# BLDC_DRIVER_DOOR.net
KiCad netlist of a schematic drawn in Altium Designer
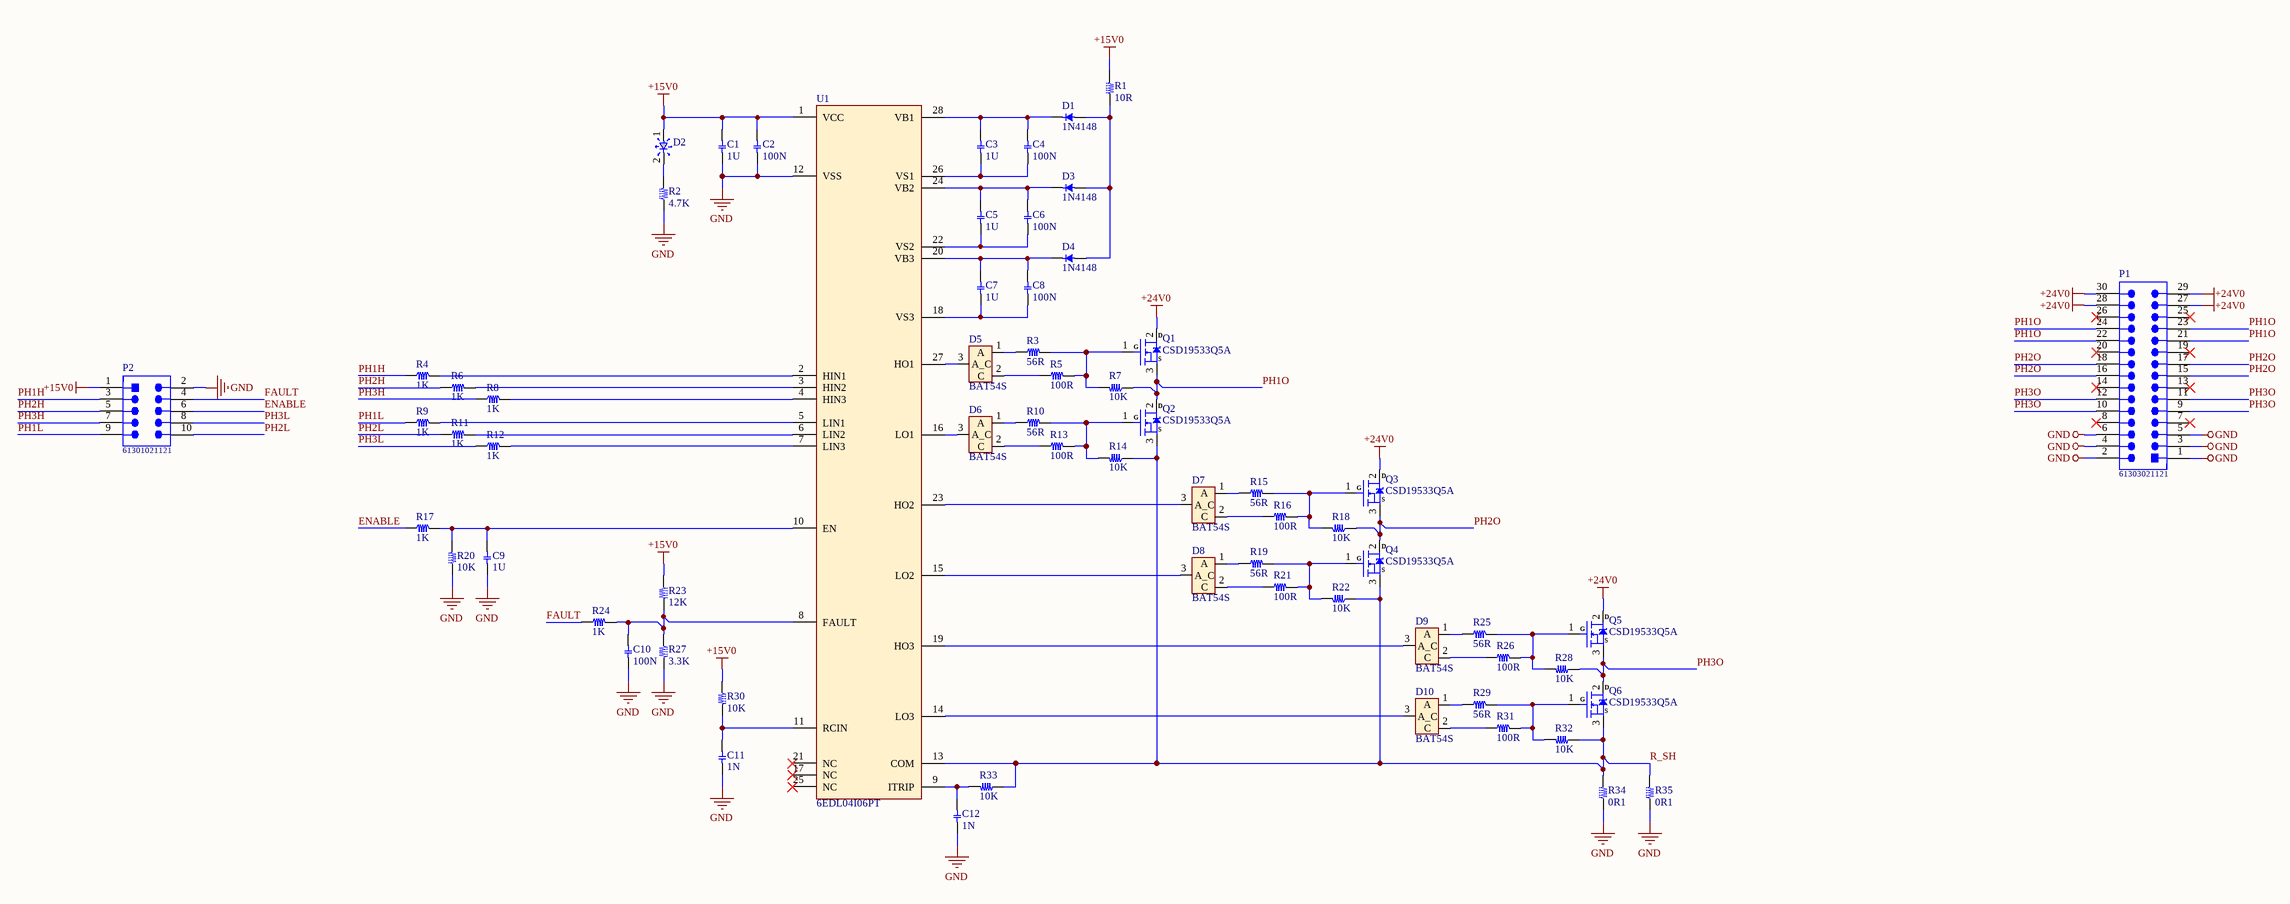
[diagram p0: BLDC_DRIVER_DOOR.SchDoc]

(export (version "E")
  (design (tool "Eeschema 10.0.6"))
  (components
    (comp (ref "C1")
      (value "1U")
      (footprint "C 0603")
      (description "CAP_SMD")
      (libsource (lib "radmehr_library") (part "CAP_SMD"))
    )
    (comp (ref "C2")
      (value "100N")
      (footprint "C 0603")
      (description "CAP_SMD")
      (libsource (lib "radmehr_library") (part "CAP_SMD"))
    )
    (comp (ref "C3")
      (value "1U")
      (footprint "C 0805")
      (description "CAP_SMD")
      (libsource (lib "radmehr_library") (part "CAP_SMD"))
    )
    (comp (ref "C4")
      (value "100N")
      (footprint "C 0805")
      (description "CAP_SMD")
      (libsource (lib "radmehr_library") (part "CAP_SMD"))
    )
    (comp (ref "C5")
      (value "1U")
      (footprint "C 0805")
      (description "CAP_SMD")
      (libsource (lib "radmehr_library") (part "CAP_SMD"))
    )
    (comp (ref "C6")
      (value "100N")
      (footprint "C 0805")
      (description "CAP_SMD")
      (libsource (lib "radmehr_library") (part "CAP_SMD"))
    )
    (comp (ref "C7")
      (value "1U")
      (footprint "C 0805")
      (description "CAP_SMD")
      (libsource (lib "radmehr_library") (part "CAP_SMD"))
    )
    (comp (ref "C8")
      (value "100N")
      (footprint "C 0805")
      (description "CAP_SMD")
      (libsource (lib "radmehr_library") (part "CAP_SMD"))
    )
    (comp (ref "C9")
      (value "1U")
      (footprint "C 0603")
      (description "CAP_SMD")
      (libsource (lib "radmehr_library") (part "CAP_SMD"))
    )
    (comp (ref "C10")
      (value "100N")
      (footprint "C 0603")
      (description "CAP_SMD")
      (libsource (lib "radmehr_library") (part "CAP_SMD"))
    )
    (comp (ref "C11")
      (value "1N")
      (footprint "C 0603")
      (description "CAP_SMD")
      (libsource (lib "radmehr_library") (part "CAP_SMD"))
    )
    (comp (ref "C12")
      (value "1N")
      (footprint "C 0805")
      (description "CAP_SMD")
      (libsource (lib "radmehr_library") (part "CAP_SMD"))
    )
    (comp (ref "D1")
      (value "1N4148")
      (footprint "D SOD-123")
      (description "DIOD_SMD")
      (libsource (lib "radmehr_library") (part "DIOD_SMD"))
    )
    (comp (ref "D2")
      (value "LED_SMD")
      (footprint "D 0603")
      (libsource (lib "radmehr_library") (part "LED_SMD"))
    )
    (comp (ref "D3")
      (value "1N4148")
      (footprint "D SOD-123")
      (description "DIOD_SMD")
      (libsource (lib "radmehr_library") (part "DIOD_SMD"))
    )
    (comp (ref "D4")
      (value "1N4148")
      (footprint "D SOD-123")
      (description "DIOD_SMD")
      (libsource (lib "radmehr_library") (part "DIOD_SMD"))
    )
    (comp (ref "D5")
      (value "BAT54S")
      (footprint "SOT-23_3_D")
      (libsource (lib "radmehr_library") (part "BAT54S"))
    )
    (comp (ref "D6")
      (value "BAT54S")
      (footprint "SOT-23_3_D")
      (libsource (lib "radmehr_library") (part "BAT54S"))
    )
    (comp (ref "D7")
      (value "BAT54S")
      (footprint "SOT-23_3_D")
      (libsource (lib "radmehr_library") (part "BAT54S"))
    )
    (comp (ref "D8")
      (value "BAT54S")
      (footprint "SOT-23_3_D")
      (libsource (lib "radmehr_library") (part "BAT54S"))
    )
    (comp (ref "D9")
      (value "BAT54S")
      (footprint "SOT-23_3_D")
      (libsource (lib "radmehr_library") (part "BAT54S"))
    )
    (comp (ref "D10")
      (value "BAT54S")
      (footprint "SOT-23_3_D")
      (libsource (lib "radmehr_library") (part "BAT54S"))
    )
    (comp (ref "P1")
      (value "61303021121")
      (footprint "61303021121")
      (description "WR-PHD Pin Header, THT, pitch 2.54mm, Dual Row, Vertical, 30p")
      (fields (field (name "MANUFACTURER") "Wurth Elektronik"))
      (libsource (lib "Altium_WR-PHD (rev22a)") (part "61303021121"))
    )
    (comp (ref "P2")
      (value "61301021121")
      (footprint "61301021121")
      (description "WR-PHD Pin Header, THT, pitch 2.54mm, Dual Row, Vertical, 10p")
      (fields (field (name "MANUFACTURER") "Wurth Elektronik"))
      (libsource (lib "Altium_WR-PHD (rev22a)") (part "61301021121"))
    )
    (comp (ref "Q1")
      (value "CSD19533Q5A")
      (footprint "Q5A")
      (libsource (lib "radmehr_library") (part "CSD19533Q5A"))
    )
    (comp (ref "Q2")
      (value "CSD19533Q5A")
      (footprint "Q5A")
      (libsource (lib "radmehr_library") (part "CSD19533Q5A"))
    )
    (comp (ref "Q3")
      (value "CSD19533Q5A")
      (footprint "Q5A")
      (libsource (lib "radmehr_library") (part "CSD19533Q5A"))
    )
    (comp (ref "Q4")
      (value "CSD19533Q5A")
      (footprint "Q5A")
      (libsource (lib "radmehr_library") (part "CSD19533Q5A"))
    )
    (comp (ref "Q5")
      (value "CSD19533Q5A")
      (footprint "Q5A")
      (libsource (lib "radmehr_library") (part "CSD19533Q5A"))
    )
    (comp (ref "Q6")
      (value "CSD19533Q5A")
      (footprint "Q5A")
      (libsource (lib "radmehr_library") (part "CSD19533Q5A"))
    )
    (comp (ref "R1")
      (value "10R")
      (footprint "R 1206")
      (description "RES_SMD")
      (libsource (lib "radmehr_library") (part "RES_SMD"))
    )
    (comp (ref "R2")
      (value "4.7K")
      (footprint "R 0603")
      (description "RES_SMD")
      (libsource (lib "radmehr_library") (part "RES_SMD"))
    )
    (comp (ref "R3")
      (value "56R")
      (footprint "R 0805")
      (description "RES_SMD")
      (libsource (lib "radmehr_library") (part "RES_SMD"))
    )
    (comp (ref "R4")
      (value "1K")
      (footprint "R 0603")
      (description "RES_SMD")
      (libsource (lib "radmehr_library") (part "RES_SMD"))
    )
    (comp (ref "R5")
      (value "100R")
      (footprint "R 0805")
      (description "RES_SMD")
      (libsource (lib "radmehr_library") (part "RES_SMD"))
    )
    (comp (ref "R6")
      (value "1K")
      (footprint "R 0603")
      (description "RES_SMD")
      (libsource (lib "radmehr_library") (part "RES_SMD"))
    )
    (comp (ref "R7")
      (value "10K")
      (footprint "R 0603")
      (description "RES_SMD")
      (libsource (lib "radmehr_library") (part "RES_SMD"))
    )
    (comp (ref "R8")
      (value "1K")
      (footprint "R 0603")
      (description "RES_SMD")
      (libsource (lib "radmehr_library") (part "RES_SMD"))
    )
    (comp (ref "R9")
      (value "1K")
      (footprint "R 0603")
      (description "RES_SMD")
      (libsource (lib "radmehr_library") (part "RES_SMD"))
    )
    (comp (ref "R10")
      (value "56R")
      (footprint "R 0805")
      (description "RES_SMD")
      (libsource (lib "radmehr_library") (part "RES_SMD"))
    )
    (comp (ref "R11")
      (value "1K")
      (footprint "R 0603")
      (description "RES_SMD")
      (libsource (lib "radmehr_library") (part "RES_SMD"))
    )
    (comp (ref "R12")
      (value "1K")
      (footprint "R 0603")
      (description "RES_SMD")
      (libsource (lib "radmehr_library") (part "RES_SMD"))
    )
    (comp (ref "R13")
      (value "100R")
      (footprint "R 0805")
      (description "RES_SMD")
      (libsource (lib "radmehr_library") (part "RES_SMD"))
    )
    (comp (ref "R14")
      (value "10K")
      (footprint "R 0603")
      (description "RES_SMD")
      (libsource (lib "radmehr_library") (part "RES_SMD"))
    )
    (comp (ref "R15")
      (value "56R")
      (footprint "R 0805")
      (description "RES_SMD")
      (libsource (lib "radmehr_library") (part "RES_SMD"))
    )
    (comp (ref "R16")
      (value "100R")
      (footprint "R 0805")
      (description "RES_SMD")
      (libsource (lib "radmehr_library") (part "RES_SMD"))
    )
    (comp (ref "R17")
      (value "1K")
      (footprint "R 0603")
      (description "RES_SMD")
      (libsource (lib "radmehr_library") (part "RES_SMD"))
    )
    (comp (ref "R18")
      (value "10K")
      (footprint "R 0603")
      (description "RES_SMD")
      (libsource (lib "radmehr_library") (part "RES_SMD"))
    )
    (comp (ref "R19")
      (value "56R")
      (footprint "R 0805")
      (description "RES_SMD")
      (libsource (lib "radmehr_library") (part "RES_SMD"))
    )
    (comp (ref "R20")
      (value "10K")
      (footprint "R 0603")
      (description "RES_SMD")
      (libsource (lib "radmehr_library") (part "RES_SMD"))
    )
    (comp (ref "R21")
      (value "100R")
      (footprint "R 0805")
      (description "RES_SMD")
      (libsource (lib "radmehr_library") (part "RES_SMD"))
    )
    (comp (ref "R22")
      (value "10K")
      (footprint "R 0603")
      (description "RES_SMD")
      (libsource (lib "radmehr_library") (part "RES_SMD"))
    )
    (comp (ref "R23")
      (value "12K")
      (footprint "R 0603")
      (description "RES_SMD")
      (libsource (lib "radmehr_library") (part "RES_SMD"))
    )
    (comp (ref "R24")
      (value "1K")
      (footprint "R 0603")
      (description "RES_SMD")
      (libsource (lib "radmehr_library") (part "RES_SMD"))
    )
    (comp (ref "R25")
      (value "56R")
      (footprint "R 0805")
      (description "RES_SMD")
      (libsource (lib "radmehr_library") (part "RES_SMD"))
    )
    (comp (ref "R26")
      (value "100R")
      (footprint "R 0805")
      (description "RES_SMD")
      (libsource (lib "radmehr_library") (part "RES_SMD"))
    )
    (comp (ref "R27")
      (value "3.3K")
      (footprint "R 0603")
      (description "RES_SMD")
      (libsource (lib "radmehr_library") (part "RES_SMD"))
    )
    (comp (ref "R28")
      (value "10K")
      (footprint "R 0603")
      (description "RES_SMD")
      (libsource (lib "radmehr_library") (part "RES_SMD"))
    )
    (comp (ref "R29")
      (value "56R")
      (footprint "R 0805")
      (description "RES_SMD")
      (libsource (lib "radmehr_library") (part "RES_SMD"))
    )
    (comp (ref "R30")
      (value "10K")
      (footprint "R 0603")
      (description "RES_SMD")
      (libsource (lib "radmehr_library") (part "RES_SMD"))
    )
    (comp (ref "R31")
      (value "100R")
      (footprint "R 0805")
      (description "RES_SMD")
      (libsource (lib "radmehr_library") (part "RES_SMD"))
    )
    (comp (ref "R32")
      (value "10K")
      (footprint "R 0603")
      (description "RES_SMD")
      (libsource (lib "radmehr_library") (part "RES_SMD"))
    )
    (comp (ref "R33")
      (value "10K")
      (footprint "R 0805")
      (description "RES_SMD")
      (libsource (lib "radmehr_library") (part "RES_SMD"))
    )
    (comp (ref "R34")
      (value "0R1")
      (footprint "R 2512")
      (description "RES_SMD")
      (libsource (lib "radmehr_library") (part "RES_SMD"))
    )
    (comp (ref "R35")
      (value "0R1")
      (footprint "R 2512")
      (description "RES_SMD")
      (libsource (lib "radmehr_library") (part "RES_SMD"))
    )
    (comp (ref "U1")
      (value "6EDL04I06PT")
      (footprint "SOIC-28")
      (libsource (lib "radmehr_library") (part "6EDL04I06PT"))
    )
  )
  (nets
    (net (code "1") (name "+15V0") (class "Default")
      (node (ref "C1") (pin "2") (pinfunction "2_2") (pintype "passive"))
      (node (ref "C2") (pin "2") (pinfunction "2_2") (pintype "passive"))
      (node (ref "D2") (pin "1") (pintype "passive"))
      (node (ref "P2") (pin "1") (pinfunction "1_1") (pintype "passive"))
      (node (ref "R1") (pin "2") (pinfunction "2_2") (pintype "passive"))
      (node (ref "R23") (pin "1") (pinfunction "1_1") (pintype "passive"))
      (node (ref "R30") (pin "1") (pinfunction "1_1") (pintype "passive"))
      (node (ref "U1") (pin "1") (pinfunction "VCC_1") (pintype "passive"))
    )
    (net (code "2") (name "+24V0") (class "Default")
      (node (ref "P1") (pin "27") (pinfunction "27_27") (pintype "passive"))
      (node (ref "P1") (pin "28") (pinfunction "28_28") (pintype "passive"))
      (node (ref "P1") (pin "29") (pinfunction "29_29") (pintype "passive"))
      (node (ref "P1") (pin "30") (pinfunction "30_30") (pintype "passive"))
      (node (ref "Q1") (pin "2") (pinfunction "D_2") (pintype "passive"))
      (node (ref "Q3") (pin "2") (pinfunction "D_2") (pintype "passive"))
      (node (ref "Q5") (pin "2") (pinfunction "D_2") (pintype "passive"))
    )
    (net (code "3") (name "/ENABLE") (class "Default")
      (node (ref "P2") (pin "6") (pinfunction "6_6") (pintype "passive"))
      (node (ref "R17") (pin "1") (pinfunction "1_1") (pintype "passive"))
    )
    (net (code "4") (name "/FAULT") (class "Default")
      (node (ref "P2") (pin "4") (pinfunction "4_4") (pintype "passive"))
      (node (ref "R24") (pin "1") (pinfunction "1_1") (pintype "passive"))
    )
    (net (code "5") (name "/PH1H") (class "Default")
      (node (ref "P2") (pin "3") (pinfunction "3_3") (pintype "passive"))
      (node (ref "R4") (pin "1") (pinfunction "1_1") (pintype "passive"))
    )
    (net (code "6") (name "/PH1L") (class "Default")
      (node (ref "P2") (pin "9") (pinfunction "9_9") (pintype "passive"))
      (node (ref "R9") (pin "1") (pinfunction "1_1") (pintype "passive"))
    )
    (net (code "7") (name "/PH1O") (class "Default")
      (node (ref "P1") (pin "21") (pinfunction "21_21") (pintype "passive"))
      (node (ref "P1") (pin "22") (pinfunction "22_22") (pintype "passive"))
      (node (ref "P1") (pin "23") (pinfunction "23_23") (pintype "passive"))
      (node (ref "P1") (pin "24") (pinfunction "24_24") (pintype "passive"))
      (node (ref "Q1") (pin "3") (pinfunction "S_3") (pintype "passive"))
      (node (ref "Q2") (pin "2") (pinfunction "D_2") (pintype "passive"))
      (node (ref "R7") (pin "1") (pinfunction "1_1") (pintype "passive"))
    )
    (net (code "8") (name "/PH2H") (class "Default")
      (node (ref "P2") (pin "5") (pinfunction "5_5") (pintype "passive"))
      (node (ref "R6") (pin "1") (pinfunction "1_1") (pintype "passive"))
    )
    (net (code "9") (name "/PH2L") (class "Default")
      (node (ref "P2") (pin "10") (pinfunction "10_10") (pintype "passive"))
      (node (ref "R11") (pin "1") (pinfunction "1_1") (pintype "passive"))
    )
    (net (code "10") (name "/PH2O") (class "Default")
      (node (ref "P1") (pin "15") (pinfunction "15_15") (pintype "passive"))
      (node (ref "P1") (pin "16") (pinfunction "16_16") (pintype "passive"))
      (node (ref "P1") (pin "17") (pinfunction "17_17") (pintype "passive"))
      (node (ref "P1") (pin "18") (pinfunction "18_18") (pintype "passive"))
      (node (ref "Q3") (pin "3") (pinfunction "S_3") (pintype "passive"))
      (node (ref "Q4") (pin "2") (pinfunction "D_2") (pintype "passive"))
      (node (ref "R18") (pin "1") (pinfunction "1_1") (pintype "passive"))
    )
    (net (code "11") (name "/PH3H") (class "Default")
      (node (ref "P2") (pin "7") (pinfunction "7_7") (pintype "passive"))
      (node (ref "R8") (pin "1") (pinfunction "1_1") (pintype "passive"))
    )
    (net (code "12") (name "/PH3L") (class "Default")
      (node (ref "P2") (pin "8") (pinfunction "8_8") (pintype "passive"))
      (node (ref "R12") (pin "1") (pinfunction "1_1") (pintype "passive"))
    )
    (net (code "13") (name "/PH3O") (class "Default")
      (node (ref "P1") (pin "10") (pinfunction "10_10") (pintype "passive"))
      (node (ref "P1") (pin "11") (pinfunction "11_11") (pintype "passive"))
      (node (ref "P1") (pin "12") (pinfunction "12_12") (pintype "passive"))
      (node (ref "P1") (pin "9") (pinfunction "9_9") (pintype "passive"))
      (node (ref "Q5") (pin "3") (pinfunction "S_3") (pintype "passive"))
      (node (ref "Q6") (pin "2") (pinfunction "D_2") (pintype "passive"))
      (node (ref "R28") (pin "1") (pinfunction "1_1") (pintype "passive"))
    )
    (net (code "14") (name "/R_SH") (class "Default")
      (node (ref "Q2") (pin "3") (pinfunction "S_3") (pintype "passive"))
      (node (ref "Q4") (pin "3") (pinfunction "S_3") (pintype "passive"))
      (node (ref "Q6") (pin "3") (pinfunction "S_3") (pintype "passive"))
      (node (ref "R14") (pin "1") (pinfunction "1_1") (pintype "passive"))
      (node (ref "R22") (pin "1") (pinfunction "1_1") (pintype "passive"))
      (node (ref "R32") (pin "1") (pinfunction "1_1") (pintype "passive"))
      (node (ref "R33") (pin "1") (pinfunction "1_1") (pintype "passive"))
      (node (ref "R34") (pin "2") (pinfunction "2_2") (pintype "passive"))
      (node (ref "R35") (pin "2") (pinfunction "2_2") (pintype "passive"))
      (node (ref "U1") (pin "13") (pinfunction "COM_13") (pintype "passive"))
    )
    (net (code "15") (name "GND") (class "Default")
      (node (ref "C1") (pin "1") (pinfunction "1_1") (pintype "passive"))
      (node (ref "C10") (pin "1") (pinfunction "1_1") (pintype "passive"))
      (node (ref "C11") (pin "1") (pinfunction "1_1") (pintype "passive"))
      (node (ref "C12") (pin "1") (pinfunction "1_1") (pintype "passive"))
      (node (ref "C2") (pin "1") (pinfunction "1_1") (pintype "passive"))
      (node (ref "C9") (pin "1") (pinfunction "1_1") (pintype "passive"))
      (node (ref "P1") (pin "1") (pinfunction "1_1") (pintype "passive"))
      (node (ref "P1") (pin "2") (pinfunction "2_2") (pintype "passive"))
      (node (ref "P1") (pin "3") (pinfunction "3_3") (pintype "passive"))
      (node (ref "P1") (pin "4") (pinfunction "4_4") (pintype "passive"))
      (node (ref "P1") (pin "5") (pinfunction "5_5") (pintype "passive"))
      (node (ref "P1") (pin "6") (pinfunction "6_6") (pintype "passive"))
      (node (ref "P2") (pin "2") (pinfunction "2_2") (pintype "passive"))
      (node (ref "R2") (pin "1") (pinfunction "1_1") (pintype "passive"))
      (node (ref "R20") (pin "1") (pinfunction "1_1") (pintype "passive"))
      (node (ref "R27") (pin "2") (pinfunction "2_2") (pintype "passive"))
      (node (ref "R34") (pin "1") (pinfunction "1_1") (pintype "passive"))
      (node (ref "R35") (pin "1") (pinfunction "1_1") (pintype "passive"))
      (node (ref "U1") (pin "12") (pinfunction "VSS_12") (pintype "passive"))
    )
    (net (code "16") (name "Net-(D1-Pad1)") (class "Default")
      (node (ref "D1") (pin "1") (pinfunction "1_1") (pintype "passive"))
      (node (ref "D3") (pin "1") (pinfunction "1_1") (pintype "passive"))
      (node (ref "D4") (pin "1") (pinfunction "1_1") (pintype "passive"))
      (node (ref "R1") (pin "1") (pinfunction "1_1") (pintype "passive"))
    )
    (net (code "17") (name "Net-(D2-Pad2)") (class "Default")
      (node (ref "D2") (pin "2") (pintype "passive"))
      (node (ref "R2") (pin "2") (pinfunction "2_2") (pintype "passive"))
    )
    (net (code "18") (name "Net-(D5-A)") (class "Default")
      (node (ref "D5") (pin "1") (pinfunction "A_1") (pintype "passive"))
      (node (ref "R3") (pin "1") (pinfunction "1_1") (pintype "passive"))
    )
    (net (code "19") (name "Net-(D5-A_C)") (class "Default")
      (node (ref "D5") (pin "3") (pinfunction "A_C_3") (pintype "passive"))
      (node (ref "U1") (pin "27") (pinfunction "HO1_27") (pintype "passive"))
    )
    (net (code "20") (name "Net-(D5-C)") (class "Default")
      (node (ref "D5") (pin "2") (pinfunction "C_2") (pintype "passive"))
      (node (ref "R5") (pin "1") (pinfunction "1_1") (pintype "passive"))
    )
    (net (code "21") (name "Net-(D6-A)") (class "Default")
      (node (ref "D6") (pin "1") (pinfunction "A_1") (pintype "passive"))
      (node (ref "R10") (pin "1") (pinfunction "1_1") (pintype "passive"))
    )
    (net (code "22") (name "Net-(D6-A_C)") (class "Default")
      (node (ref "D6") (pin "3") (pinfunction "A_C_3") (pintype "passive"))
      (node (ref "U1") (pin "16") (pinfunction "LO1_16") (pintype "passive"))
    )
    (net (code "23") (name "Net-(D6-C)") (class "Default")
      (node (ref "D6") (pin "2") (pinfunction "C_2") (pintype "passive"))
      (node (ref "R13") (pin "1") (pinfunction "1_1") (pintype "passive"))
    )
    (net (code "24") (name "Net-(D7-A)") (class "Default")
      (node (ref "D7") (pin "1") (pinfunction "A_1") (pintype "passive"))
      (node (ref "R15") (pin "1") (pinfunction "1_1") (pintype "passive"))
    )
    (net (code "25") (name "Net-(D7-A_C)") (class "Default")
      (node (ref "D7") (pin "3") (pinfunction "A_C_3") (pintype "passive"))
      (node (ref "U1") (pin "23") (pinfunction "HO2_23") (pintype "passive"))
    )
    (net (code "26") (name "Net-(D7-C)") (class "Default")
      (node (ref "D7") (pin "2") (pinfunction "C_2") (pintype "passive"))
      (node (ref "R16") (pin "1") (pinfunction "1_1") (pintype "passive"))
    )
    (net (code "27") (name "Net-(D8-A)") (class "Default")
      (node (ref "D8") (pin "1") (pinfunction "A_1") (pintype "passive"))
      (node (ref "R19") (pin "1") (pinfunction "1_1") (pintype "passive"))
    )
    (net (code "28") (name "Net-(D8-A_C)") (class "Default")
      (node (ref "D8") (pin "3") (pinfunction "A_C_3") (pintype "passive"))
      (node (ref "U1") (pin "15") (pinfunction "LO2_15") (pintype "passive"))
    )
    (net (code "29") (name "Net-(D8-C)") (class "Default")
      (node (ref "D8") (pin "2") (pinfunction "C_2") (pintype "passive"))
      (node (ref "R21") (pin "1") (pinfunction "1_1") (pintype "passive"))
    )
    (net (code "30") (name "Net-(D9-A)") (class "Default")
      (node (ref "D9") (pin "1") (pinfunction "A_1") (pintype "passive"))
      (node (ref "R25") (pin "1") (pinfunction "1_1") (pintype "passive"))
    )
    (net (code "31") (name "Net-(D9-A_C)") (class "Default")
      (node (ref "D9") (pin "3") (pinfunction "A_C_3") (pintype "passive"))
      (node (ref "U1") (pin "19") (pinfunction "HO3_19") (pintype "passive"))
    )
    (net (code "32") (name "Net-(D9-C)") (class "Default")
      (node (ref "D9") (pin "2") (pinfunction "C_2") (pintype "passive"))
      (node (ref "R26") (pin "1") (pinfunction "1_1") (pintype "passive"))
    )
    (net (code "33") (name "Net-(D10-A)") (class "Default")
      (node (ref "D10") (pin "1") (pinfunction "A_1") (pintype "passive"))
      (node (ref "R29") (pin "1") (pinfunction "1_1") (pintype "passive"))
    )
    (net (code "34") (name "Net-(D10-A_C)") (class "Default")
      (node (ref "D10") (pin "3") (pinfunction "A_C_3") (pintype "passive"))
      (node (ref "U1") (pin "14") (pinfunction "LO3_14") (pintype "passive"))
    )
    (net (code "35") (name "Net-(D10-C)") (class "Default")
      (node (ref "D10") (pin "2") (pinfunction "C_2") (pintype "passive"))
      (node (ref "R31") (pin "1") (pinfunction "1_1") (pintype "passive"))
    )
    (net (code "36") (name "Net-(Q1-G)") (class "Default")
      (node (ref "Q1") (pin "1") (pinfunction "G_1") (pintype "passive"))
      (node (ref "R3") (pin "2") (pinfunction "2_2") (pintype "passive"))
      (node (ref "R5") (pin "2") (pinfunction "2_2") (pintype "passive"))
      (node (ref "R7") (pin "2") (pinfunction "2_2") (pintype "passive"))
    )
    (net (code "37") (name "Net-(Q2-G)") (class "Default")
      (node (ref "Q2") (pin "1") (pinfunction "G_1") (pintype "passive"))
      (node (ref "R10") (pin "2") (pinfunction "2_2") (pintype "passive"))
      (node (ref "R13") (pin "2") (pinfunction "2_2") (pintype "passive"))
      (node (ref "R14") (pin "2") (pinfunction "2_2") (pintype "passive"))
    )
    (net (code "38") (name "Net-(Q3-G)") (class "Default")
      (node (ref "Q3") (pin "1") (pinfunction "G_1") (pintype "passive"))
      (node (ref "R15") (pin "2") (pinfunction "2_2") (pintype "passive"))
      (node (ref "R16") (pin "2") (pinfunction "2_2") (pintype "passive"))
      (node (ref "R18") (pin "2") (pinfunction "2_2") (pintype "passive"))
    )
    (net (code "39") (name "Net-(Q4-G)") (class "Default")
      (node (ref "Q4") (pin "1") (pinfunction "G_1") (pintype "passive"))
      (node (ref "R19") (pin "2") (pinfunction "2_2") (pintype "passive"))
      (node (ref "R21") (pin "2") (pinfunction "2_2") (pintype "passive"))
      (node (ref "R22") (pin "2") (pinfunction "2_2") (pintype "passive"))
    )
    (net (code "40") (name "Net-(Q5-G)") (class "Default")
      (node (ref "Q5") (pin "1") (pinfunction "G_1") (pintype "passive"))
      (node (ref "R25") (pin "2") (pinfunction "2_2") (pintype "passive"))
      (node (ref "R26") (pin "2") (pinfunction "2_2") (pintype "passive"))
      (node (ref "R28") (pin "2") (pinfunction "2_2") (pintype "passive"))
    )
    (net (code "41") (name "Net-(Q6-G)") (class "Default")
      (node (ref "Q6") (pin "1") (pinfunction "G_1") (pintype "passive"))
      (node (ref "R29") (pin "2") (pinfunction "2_2") (pintype "passive"))
      (node (ref "R31") (pin "2") (pinfunction "2_2") (pintype "passive"))
      (node (ref "R32") (pin "2") (pinfunction "2_2") (pintype "passive"))
    )
    (net (code "42") (name "Net-(U1-EN)") (class "Default")
      (node (ref "C9") (pin "2") (pinfunction "2_2") (pintype "passive"))
      (node (ref "R17") (pin "2") (pinfunction "2_2") (pintype "passive"))
      (node (ref "R20") (pin "2") (pinfunction "2_2") (pintype "passive"))
      (node (ref "U1") (pin "10") (pinfunction "EN_10") (pintype "passive"))
    )
    (net (code "43") (name "Net-(U1-FAULT)") (class "Default")
      (node (ref "C10") (pin "2") (pinfunction "2_2") (pintype "passive"))
      (node (ref "R23") (pin "2") (pinfunction "2_2") (pintype "passive"))
      (node (ref "R24") (pin "2") (pinfunction "2_2") (pintype "passive"))
      (node (ref "R27") (pin "1") (pinfunction "1_1") (pintype "passive"))
      (node (ref "U1") (pin "8") (pinfunction "FAULT_8") (pintype "passive"))
    )
    (net (code "44") (name "Net-(U1-HIN1)") (class "Default")
      (node (ref "R4") (pin "2") (pinfunction "2_2") (pintype "passive"))
      (node (ref "U1") (pin "2") (pinfunction "HIN1_2") (pintype "passive"))
    )
    (net (code "45") (name "Net-(U1-HIN2)") (class "Default")
      (node (ref "R6") (pin "2") (pinfunction "2_2") (pintype "passive"))
      (node (ref "U1") (pin "3") (pinfunction "HIN2_3") (pintype "passive"))
    )
    (net (code "46") (name "Net-(U1-HIN3)") (class "Default")
      (node (ref "R8") (pin "2") (pinfunction "2_2") (pintype "passive"))
      (node (ref "U1") (pin "4") (pinfunction "HIN3_4") (pintype "passive"))
    )
    (net (code "47") (name "Net-(U1-ITRIP)") (class "Default")
      (node (ref "C12") (pin "2") (pinfunction "2_2") (pintype "passive"))
      (node (ref "R33") (pin "2") (pinfunction "2_2") (pintype "passive"))
      (node (ref "U1") (pin "9") (pinfunction "ITRIP_9") (pintype "passive"))
    )
    (net (code "48") (name "Net-(U1-LIN1)") (class "Default")
      (node (ref "R9") (pin "2") (pinfunction "2_2") (pintype "passive"))
      (node (ref "U1") (pin "5") (pinfunction "LIN1_5") (pintype "passive"))
    )
    (net (code "49") (name "Net-(U1-LIN2)") (class "Default")
      (node (ref "R11") (pin "2") (pinfunction "2_2") (pintype "passive"))
      (node (ref "U1") (pin "6") (pinfunction "LIN2_6") (pintype "passive"))
    )
    (net (code "50") (name "Net-(U1-LIN3)") (class "Default")
      (node (ref "R12") (pin "2") (pinfunction "2_2") (pintype "passive"))
      (node (ref "U1") (pin "7") (pinfunction "LIN3_7") (pintype "passive"))
    )
    (net (code "51") (name "Net-(U1-RCIN)") (class "Default")
      (node (ref "C11") (pin "2") (pinfunction "2_2") (pintype "passive"))
      (node (ref "R30") (pin "2") (pinfunction "2_2") (pintype "passive"))
      (node (ref "U1") (pin "11") (pinfunction "RCIN_11") (pintype "passive"))
    )
    (net (code "52") (name "Net-(U1-VB1)") (class "Default")
      (node (ref "C3") (pin "2") (pinfunction "2_2") (pintype "passive"))
      (node (ref "C4") (pin "2") (pinfunction "2_2") (pintype "passive"))
      (node (ref "D1") (pin "2") (pinfunction "2_2") (pintype "passive"))
      (node (ref "U1") (pin "28") (pinfunction "VB1_28") (pintype "passive"))
    )
    (net (code "53") (name "Net-(U1-VB2)") (class "Default")
      (node (ref "C5") (pin "2") (pinfunction "2_2") (pintype "passive"))
      (node (ref "C6") (pin "2") (pinfunction "2_2") (pintype "passive"))
      (node (ref "D3") (pin "2") (pinfunction "2_2") (pintype "passive"))
      (node (ref "U1") (pin "24") (pinfunction "VB2_24") (pintype "passive"))
    )
    (net (code "54") (name "Net-(U1-VB3)") (class "Default")
      (node (ref "C7") (pin "2") (pinfunction "2_2") (pintype "passive"))
      (node (ref "C8") (pin "2") (pinfunction "2_2") (pintype "passive"))
      (node (ref "D4") (pin "2") (pinfunction "2_2") (pintype "passive"))
      (node (ref "U1") (pin "20") (pinfunction "VB3_20") (pintype "passive"))
    )
    (net (code "55") (name "Net-(U1-VS1)") (class "Default")
      (node (ref "C3") (pin "1") (pinfunction "1_1") (pintype "passive"))
      (node (ref "C4") (pin "1") (pinfunction "1_1") (pintype "passive"))
      (node (ref "U1") (pin "26") (pinfunction "VS1_26") (pintype "passive"))
    )
    (net (code "56") (name "Net-(U1-VS2)") (class "Default")
      (node (ref "C5") (pin "1") (pinfunction "1_1") (pintype "passive"))
      (node (ref "C6") (pin "1") (pinfunction "1_1") (pintype "passive"))
      (node (ref "U1") (pin "22") (pinfunction "VS2_22") (pintype "passive"))
    )
    (net (code "57") (name "Net-(U1-VS3)") (class "Default")
      (node (ref "C7") (pin "1") (pinfunction "1_1") (pintype "passive"))
      (node (ref "C8") (pin "1") (pinfunction "1_1") (pintype "passive"))
      (node (ref "U1") (pin "18") (pinfunction "VS3_18") (pintype "passive"))
    )
    (net (code "58") (name "unconnected-(P1-Pad7)") (class "Default")
      (node (ref "P1") (pin "7") (pinfunction "7_7") (pintype "passive+no_connect"))
    )
    (net (code "59") (name "unconnected-(P1-Pad8)") (class "Default")
      (node (ref "P1") (pin "8") (pinfunction "8_8") (pintype "passive+no_connect"))
    )
    (net (code "60") (name "unconnected-(P1-Pad13)") (class "Default")
      (node (ref "P1") (pin "13") (pinfunction "13_13") (pintype "passive+no_connect"))
    )
    (net (code "61") (name "unconnected-(P1-Pad14)") (class "Default")
      (node (ref "P1") (pin "14") (pinfunction "14_14") (pintype "passive+no_connect"))
    )
    (net (code "62") (name "unconnected-(P1-Pad19)") (class "Default")
      (node (ref "P1") (pin "19") (pinfunction "19_19") (pintype "passive+no_connect"))
    )
    (net (code "63") (name "unconnected-(P1-Pad20)") (class "Default")
      (node (ref "P1") (pin "20") (pinfunction "20_20") (pintype "passive+no_connect"))
    )
    (net (code "64") (name "unconnected-(P1-Pad25)") (class "Default")
      (node (ref "P1") (pin "25") (pinfunction "25_25") (pintype "passive+no_connect"))
    )
    (net (code "65") (name "unconnected-(P1-Pad26)") (class "Default")
      (node (ref "P1") (pin "26") (pinfunction "26_26") (pintype "passive+no_connect"))
    )
    (net (code "66") (name "unconnected-(U1-NC-Pad17)") (class "Default")
      (node (ref "U1") (pin "17") (pinfunction "NC_17") (pintype "passive+no_connect"))
    )
    (net (code "67") (name "unconnected-(U1-NC-Pad21)") (class "Default")
      (node (ref "U1") (pin "21") (pinfunction "NC_21") (pintype "passive+no_connect"))
    )
    (net (code "68") (name "unconnected-(U1-NC-Pad25)") (class "Default")
      (node (ref "U1") (pin "25") (pinfunction "NC_25") (pintype "passive+no_connect"))
    )
  )
)
